# rover_5.net
KiCad netlist of a schematic drawn in EAGLE
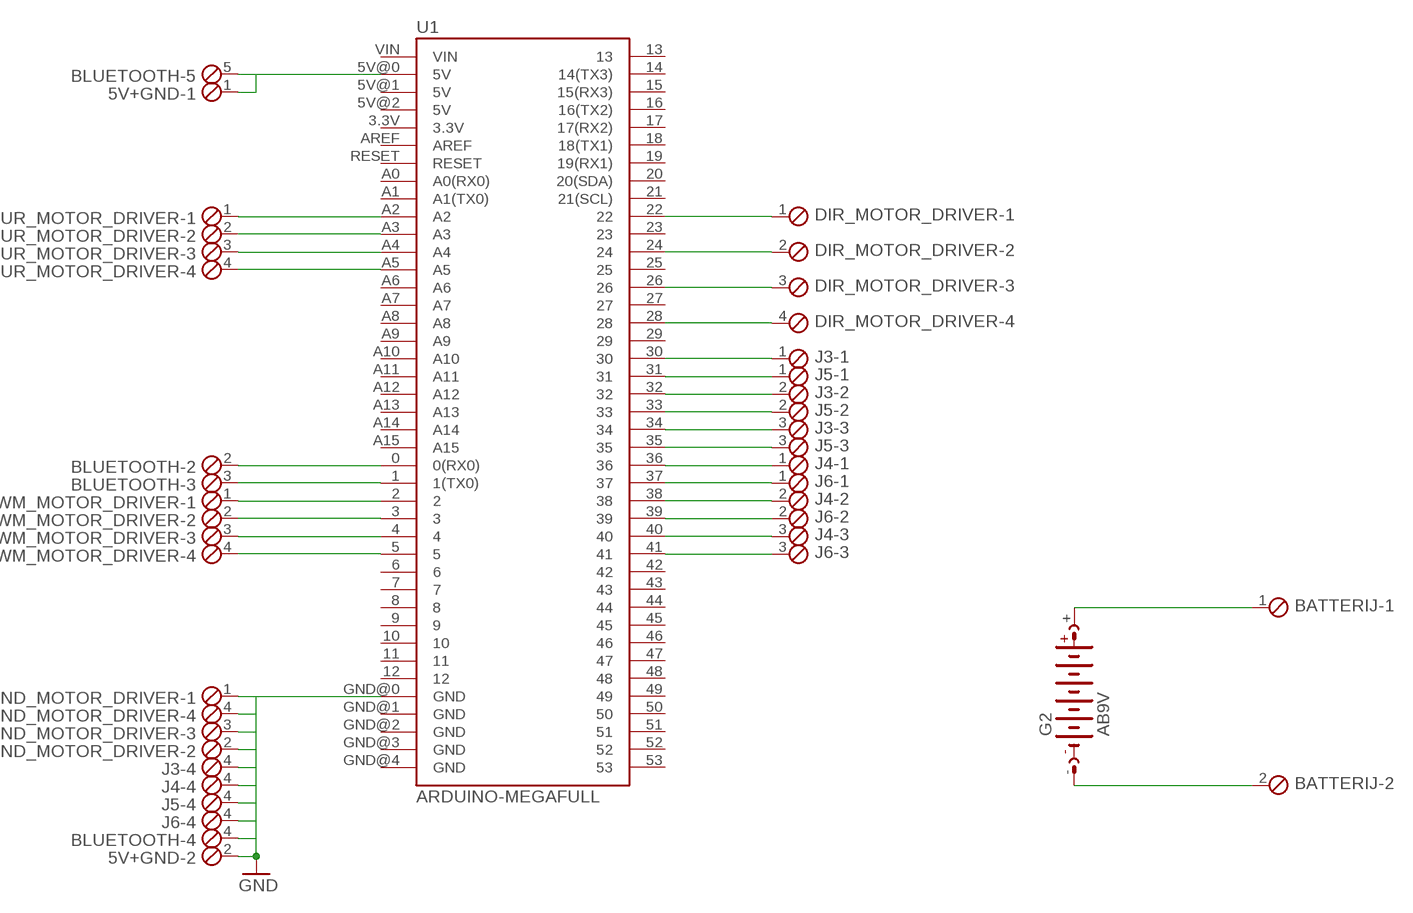
[diagram p0: schematic, sheet 1]

(export (version "E")
  (design (tool "Eeschema 10.0.6"))
  (components
    (comp (ref "5V+GND")
      (value "MPT2")
      (footprint "eagle-import:2POL254")
      (libsource (lib "eagle-import") (part "MPT2"))
    )
    (comp (ref "BATTERIJ")
      (value "MPT2")
      (footprint "eagle-import:2POL254")
      (libsource (lib "eagle-import") (part "MPT2"))
    )
    (comp (ref "BLUETOOTH")
      (value "MPT6")
      (footprint "eagle-import:6POL254")
      (libsource (lib "eagle-import") (part "MPT6"))
    )
    (comp (ref "CUR_MOTOR_DRIVER")
      (value "MPT4")
      (footprint "eagle-import:4POL254")
      (libsource (lib "eagle-import") (part "MPT4"))
    )
    (comp (ref "DIR_MOTOR_DRIVER")
      (value "MPT4")
      (footprint "eagle-import:4POL254")
      (libsource (lib "eagle-import") (part "MPT4"))
    )
    (comp (ref "G2")
      (value "AB9V")
      (footprint "eagle-import:AB9V")
      (libsource (lib "eagle-import") (part "AB9V"))
    )
    (comp (ref "GND_MOTOR_DRIVER")
      (value "MPT4")
      (footprint "eagle-import:4POL254")
      (libsource (lib "eagle-import") (part "MPT4"))
    )
    (comp (ref "J3")
      (value "MPT4")
      (footprint "eagle-import:4POL254")
      (libsource (lib "eagle-import") (part "MPT4"))
    )
    (comp (ref "J4")
      (value "MPT4")
      (footprint "eagle-import:4POL254")
      (libsource (lib "eagle-import") (part "MPT4"))
    )
    (comp (ref "J5")
      (value "MPT4")
      (footprint "eagle-import:4POL254")
      (libsource (lib "eagle-import") (part "MPT4"))
    )
    (comp (ref "J6")
      (value "MPT4")
      (footprint "eagle-import:4POL254")
      (libsource (lib "eagle-import") (part "MPT4"))
    )
    (comp (ref "PWM_MOTOR_DRIVER")
      (value "MPT4")
      (footprint "eagle-import:4POL254")
      (libsource (lib "eagle-import") (part "MPT4"))
    )
    (comp (ref "U1")
      (value "ARDUINO-MEGAFULL")
      (footprint "eagle-import:ARDUINO_MEGA")
      (libsource (lib "eagle-import") (part "ARDUINO-MEGAFULL"))
    )
  )
  (nets
    (net (code "1") (name "GND") (class "Default")
      (node (ref "5V+GND") (pin "2") (pinfunction "1_2") (pintype "passive"))
      (node (ref "BLUETOOTH") (pin "4") (pinfunction "1_4") (pintype "passive"))
      (node (ref "GND_MOTOR_DRIVER") (pin "1") (pinfunction "1_1") (pintype "passive"))
      (node (ref "GND_MOTOR_DRIVER") (pin "2") (pinfunction "1_2") (pintype "passive"))
      (node (ref "GND_MOTOR_DRIVER") (pin "3") (pinfunction "1_3") (pintype "passive"))
      (node (ref "GND_MOTOR_DRIVER") (pin "4") (pinfunction "1_4") (pintype "passive"))
      (node (ref "J3") (pin "4") (pinfunction "1_4") (pintype "passive"))
      (node (ref "J4") (pin "4") (pinfunction "1_4") (pintype "passive"))
      (node (ref "J5") (pin "4") (pinfunction "1_4") (pintype "passive"))
      (node (ref "J6") (pin "4") (pinfunction "1_4") (pintype "passive"))
      (node (ref "U1") (pin "GND@0") (pinfunction "GND_GND@0") (pintype "bidirectional"))
    )
    (net (code "2") (name "Net-(BATTERIJ-Pad1)") (class "Default")
      (node (ref "BATTERIJ") (pin "1") (pinfunction "1_1") (pintype "passive"))
      (node (ref "G2") (pin "+") (pinfunction "+_+") (pintype "passive"))
    )
    (net (code "3") (name "Net-(BATTERIJB-1)") (class "Default")
      (node (ref "BATTERIJ") (pin "2") (pinfunction "1_2") (pintype "passive"))
      (node (ref "G2") (pin "-") (pinfunction "-_-") (pintype "passive"))
    )
    (net (code "4") (name "Net-(BLUETOOTHB-1)") (class "Default")
      (node (ref "BLUETOOTH") (pin "2") (pinfunction "1_2") (pintype "passive"))
      (node (ref "U1") (pin "0") (pinfunction "0(RX0)_0") (pintype "bidirectional"))
    )
    (net (code "5") (name "Net-(BLUETOOTHC-1)") (class "Default")
      (node (ref "BLUETOOTH") (pin "3") (pinfunction "1_3") (pintype "passive"))
      (node (ref "U1") (pin "1") (pinfunction "1(TX0)_1") (pintype "bidirectional"))
    )
    (net (code "6") (name "Net-(BLUETOOTHE-1)") (class "Default")
      (node (ref "5V+GND") (pin "1") (pinfunction "1_1") (pintype "passive"))
      (node (ref "BLUETOOTH") (pin "5") (pinfunction "1_5") (pintype "passive"))
      (node (ref "U1") (pin "5V@0") (pinfunction "5V_5V@0") (pintype "bidirectional"))
    )
    (net (code "7") (name "Net-(CUR_MOTOR_DRIVER-Pad1)") (class "Default")
      (node (ref "CUR_MOTOR_DRIVER") (pin "1") (pinfunction "1_1") (pintype "passive"))
      (node (ref "U1") (pin "A2") (pinfunction "A2_A2") (pintype "bidirectional"))
    )
    (net (code "8") (name "Net-(CUR_MOTOR_DRIVERB-1)") (class "Default")
      (node (ref "CUR_MOTOR_DRIVER") (pin "2") (pinfunction "1_2") (pintype "passive"))
      (node (ref "U1") (pin "A3") (pinfunction "A3_A3") (pintype "bidirectional"))
    )
    (net (code "9") (name "Net-(CUR_MOTOR_DRIVERC-1)") (class "Default")
      (node (ref "CUR_MOTOR_DRIVER") (pin "3") (pinfunction "1_3") (pintype "passive"))
      (node (ref "U1") (pin "A4") (pinfunction "A4_A4") (pintype "bidirectional"))
    )
    (net (code "10") (name "Net-(CUR_MOTOR_DRIVERD-1)") (class "Default")
      (node (ref "CUR_MOTOR_DRIVER") (pin "4") (pinfunction "1_4") (pintype "passive"))
      (node (ref "U1") (pin "A5") (pinfunction "A5_A5") (pintype "bidirectional"))
    )
    (net (code "11") (name "Net-(DIR_MOTOR_DRIVER-Pad1)") (class "Default")
      (node (ref "DIR_MOTOR_DRIVER") (pin "1") (pinfunction "1_1") (pintype "passive"))
      (node (ref "U1") (pin "22") (pinfunction "22_22") (pintype "bidirectional"))
    )
    (net (code "12") (name "Net-(DIR_MOTOR_DRIVERB-1)") (class "Default")
      (node (ref "DIR_MOTOR_DRIVER") (pin "2") (pinfunction "1_2") (pintype "passive"))
      (node (ref "U1") (pin "24") (pinfunction "24_24") (pintype "bidirectional"))
    )
    (net (code "13") (name "Net-(DIR_MOTOR_DRIVERC-1)") (class "Default")
      (node (ref "DIR_MOTOR_DRIVER") (pin "3") (pinfunction "1_3") (pintype "passive"))
      (node (ref "U1") (pin "26") (pinfunction "26_26") (pintype "bidirectional"))
    )
    (net (code "14") (name "Net-(DIR_MOTOR_DRIVERD-1)") (class "Default")
      (node (ref "DIR_MOTOR_DRIVER") (pin "4") (pinfunction "1_4") (pintype "passive"))
      (node (ref "U1") (pin "28") (pinfunction "28_28") (pintype "bidirectional"))
    )
    (net (code "15") (name "Net-(J3-Pad1)") (class "Default")
      (node (ref "J3") (pin "1") (pinfunction "1_1") (pintype "passive"))
      (node (ref "U1") (pin "30") (pinfunction "30_30") (pintype "bidirectional"))
    )
    (net (code "16") (name "Net-(J3B-1)") (class "Default")
      (node (ref "J3") (pin "2") (pinfunction "1_2") (pintype "passive"))
      (node (ref "U1") (pin "32") (pinfunction "32_32") (pintype "bidirectional"))
    )
    (net (code "17") (name "Net-(J3C-1)") (class "Default")
      (node (ref "J3") (pin "3") (pinfunction "1_3") (pintype "passive"))
      (node (ref "U1") (pin "34") (pinfunction "34_34") (pintype "bidirectional"))
    )
    (net (code "18") (name "Net-(J4-Pad1)") (class "Default")
      (node (ref "J4") (pin "1") (pinfunction "1_1") (pintype "passive"))
      (node (ref "U1") (pin "36") (pinfunction "36_36") (pintype "bidirectional"))
    )
    (net (code "19") (name "Net-(J4B-1)") (class "Default")
      (node (ref "J4") (pin "2") (pinfunction "1_2") (pintype "passive"))
      (node (ref "U1") (pin "38") (pinfunction "38_38") (pintype "bidirectional"))
    )
    (net (code "20") (name "Net-(J4C-1)") (class "Default")
      (node (ref "J4") (pin "3") (pinfunction "1_3") (pintype "passive"))
      (node (ref "U1") (pin "40") (pinfunction "40_40") (pintype "bidirectional"))
    )
    (net (code "21") (name "Net-(J5-Pad1)") (class "Default")
      (node (ref "J5") (pin "1") (pinfunction "1_1") (pintype "passive"))
      (node (ref "U1") (pin "31") (pinfunction "31_31") (pintype "bidirectional"))
    )
    (net (code "22") (name "Net-(J5B-1)") (class "Default")
      (node (ref "J5") (pin "2") (pinfunction "1_2") (pintype "passive"))
      (node (ref "U1") (pin "33") (pinfunction "33_33") (pintype "bidirectional"))
    )
    (net (code "23") (name "Net-(J5C-1)") (class "Default")
      (node (ref "J5") (pin "3") (pinfunction "1_3") (pintype "passive"))
      (node (ref "U1") (pin "35") (pinfunction "35_35") (pintype "bidirectional"))
    )
    (net (code "24") (name "Net-(J6-Pad1)") (class "Default")
      (node (ref "J6") (pin "1") (pinfunction "1_1") (pintype "passive"))
      (node (ref "U1") (pin "37") (pinfunction "37_37") (pintype "bidirectional"))
    )
    (net (code "25") (name "Net-(J6B-1)") (class "Default")
      (node (ref "J6") (pin "2") (pinfunction "1_2") (pintype "passive"))
      (node (ref "U1") (pin "39") (pinfunction "39_39") (pintype "bidirectional"))
    )
    (net (code "26") (name "Net-(J6C-1)") (class "Default")
      (node (ref "J6") (pin "3") (pinfunction "1_3") (pintype "passive"))
      (node (ref "U1") (pin "41") (pinfunction "41_41") (pintype "bidirectional"))
    )
    (net (code "27") (name "Net-(PWM_MOTOR_DRIVER-Pad1)") (class "Default")
      (node (ref "PWM_MOTOR_DRIVER") (pin "1") (pinfunction "1_1") (pintype "passive"))
      (node (ref "U1") (pin "2") (pinfunction "2_2") (pintype "bidirectional"))
    )
    (net (code "28") (name "Net-(PWM_MOTOR_DRIVERB-1)") (class "Default")
      (node (ref "PWM_MOTOR_DRIVER") (pin "2") (pinfunction "1_2") (pintype "passive"))
      (node (ref "U1") (pin "3") (pinfunction "3_3") (pintype "bidirectional"))
    )
    (net (code "29") (name "Net-(PWM_MOTOR_DRIVERC-1)") (class "Default")
      (node (ref "PWM_MOTOR_DRIVER") (pin "3") (pinfunction "1_3") (pintype "passive"))
      (node (ref "U1") (pin "4") (pinfunction "4_4") (pintype "bidirectional"))
    )
    (net (code "30") (name "Net-(PWM_MOTOR_DRIVERD-1)") (class "Default")
      (node (ref "PWM_MOTOR_DRIVER") (pin "4") (pinfunction "1_4") (pintype "passive"))
      (node (ref "U1") (pin "5") (pinfunction "5_5") (pintype "bidirectional"))
    )
    (net (code "31") (name "unconnected-(U1-5V-Pad5V@1)") (class "Default")
      (node (ref "U1") (pin "5V@1") (pinfunction "5V_5V@1") (pintype "bidirectional"))
    )
    (net (code "32") (name "unconnected-(U1-5V-Pad5V@2)") (class "Default")
      (node (ref "U1") (pin "5V@2") (pinfunction "5V_5V@2") (pintype "bidirectional"))
    )
    (net (code "33") (name "unconnected-(U1-14(TX3)-Pad14)") (class "Default")
      (node (ref "U1") (pin "14") (pinfunction "14(TX3)_14") (pintype "bidirectional"))
    )
    (net (code "34") (name "unconnected-(U1-15(RX3)-Pad15)") (class "Default")
      (node (ref "U1") (pin "15") (pinfunction "15(RX3)_15") (pintype "bidirectional"))
    )
    (net (code "35") (name "unconnected-(U1-16(TX2)-Pad16)") (class "Default")
      (node (ref "U1") (pin "16") (pinfunction "16(TX2)_16") (pintype "bidirectional"))
    )
    (net (code "36") (name "unconnected-(U1-17(RX2)-Pad17)") (class "Default")
      (node (ref "U1") (pin "17") (pinfunction "17(RX2)_17") (pintype "bidirectional"))
    )
    (net (code "37") (name "unconnected-(U1-18(TX1)-Pad18)") (class "Default")
      (node (ref "U1") (pin "18") (pinfunction "18(TX1)_18") (pintype "bidirectional"))
    )
    (net (code "38") (name "unconnected-(U1-19(RX1)-Pad19)") (class "Default")
      (node (ref "U1") (pin "19") (pinfunction "19(RX1)_19") (pintype "bidirectional"))
    )
    (net (code "39") (name "unconnected-(U1-20(SDA)-Pad20)") (class "Default")
      (node (ref "U1") (pin "20") (pinfunction "20(SDA)_20") (pintype "bidirectional"))
    )
    (net (code "40") (name "unconnected-(U1-21(SCL)-Pad21)") (class "Default")
      (node (ref "U1") (pin "21") (pinfunction "21(SCL)_21") (pintype "bidirectional"))
    )
    (net (code "41") (name "unconnected-(U1-A0(RX0)-PadA0)") (class "Default")
      (node (ref "U1") (pin "A0") (pinfunction "A0(RX0)_A0") (pintype "bidirectional"))
    )
    (net (code "42") (name "unconnected-(U1-A1(TX0)-PadA1)") (class "Default")
      (node (ref "U1") (pin "A1") (pinfunction "A1(TX0)_A1") (pintype "bidirectional"))
    )
    (net (code "43") (name "unconnected-(U1-GND-PadGND@1)") (class "Default")
      (node (ref "U1") (pin "GND@1") (pinfunction "GND_GND@1") (pintype "bidirectional"))
    )
    (net (code "44") (name "unconnected-(U1-GND-PadGND@2)") (class "Default")
      (node (ref "U1") (pin "GND@2") (pinfunction "GND_GND@2") (pintype "bidirectional"))
    )
    (net (code "45") (name "unconnected-(U1-GND-PadGND@3)") (class "Default")
      (node (ref "U1") (pin "GND@3") (pinfunction "GND_GND@3") (pintype "bidirectional"))
    )
    (net (code "46") (name "unconnected-(U1-GND-PadGND@4)") (class "Default")
      (node (ref "U1") (pin "GND@4") (pinfunction "GND_GND@4") (pintype "bidirectional"))
    )
    (net (code "47") (name "unconnected-(U1-Pad3.3V)") (class "Default")
      (node (ref "U1") (pin "3.3V") (pinfunction "3.3V_3.3V") (pintype "bidirectional"))
    )
    (net (code "48") (name "unconnected-(U1-Pad6)") (class "Default")
      (node (ref "U1") (pin "6") (pinfunction "6_6") (pintype "bidirectional"))
    )
    (net (code "49") (name "unconnected-(U1-Pad7)") (class "Default")
      (node (ref "U1") (pin "7") (pinfunction "7_7") (pintype "bidirectional"))
    )
    (net (code "50") (name "unconnected-(U1-Pad8)") (class "Default")
      (node (ref "U1") (pin "8") (pinfunction "8_8") (pintype "bidirectional"))
    )
    (net (code "51") (name "unconnected-(U1-Pad9)") (class "Default")
      (node (ref "U1") (pin "9") (pinfunction "9_9") (pintype "bidirectional"))
    )
    (net (code "52") (name "unconnected-(U1-Pad10)") (class "Default")
      (node (ref "U1") (pin "10") (pinfunction "10_10") (pintype "bidirectional"))
    )
    (net (code "53") (name "unconnected-(U1-Pad11)") (class "Default")
      (node (ref "U1") (pin "11") (pinfunction "11_11") (pintype "bidirectional"))
    )
    (net (code "54") (name "unconnected-(U1-Pad12)") (class "Default")
      (node (ref "U1") (pin "12") (pinfunction "12_12") (pintype "bidirectional"))
    )
    (net (code "55") (name "unconnected-(U1-Pad13)") (class "Default")
      (node (ref "U1") (pin "13") (pinfunction "13_13") (pintype "bidirectional"))
    )
    (net (code "56") (name "unconnected-(U1-Pad23)") (class "Default")
      (node (ref "U1") (pin "23") (pinfunction "23_23") (pintype "bidirectional"))
    )
    (net (code "57") (name "unconnected-(U1-Pad25)") (class "Default")
      (node (ref "U1") (pin "25") (pinfunction "25_25") (pintype "bidirectional"))
    )
    (net (code "58") (name "unconnected-(U1-Pad27)") (class "Default")
      (node (ref "U1") (pin "27") (pinfunction "27_27") (pintype "bidirectional"))
    )
    (net (code "59") (name "unconnected-(U1-Pad29)") (class "Default")
      (node (ref "U1") (pin "29") (pinfunction "29_29") (pintype "bidirectional"))
    )
    (net (code "60") (name "unconnected-(U1-Pad42)") (class "Default")
      (node (ref "U1") (pin "42") (pinfunction "42_42") (pintype "bidirectional"))
    )
    (net (code "61") (name "unconnected-(U1-Pad43)") (class "Default")
      (node (ref "U1") (pin "43") (pinfunction "43_43") (pintype "bidirectional"))
    )
    (net (code "62") (name "unconnected-(U1-Pad44)") (class "Default")
      (node (ref "U1") (pin "44") (pinfunction "44_44") (pintype "bidirectional"))
    )
    (net (code "63") (name "unconnected-(U1-Pad45)") (class "Default")
      (node (ref "U1") (pin "45") (pinfunction "45_45") (pintype "bidirectional"))
    )
    (net (code "64") (name "unconnected-(U1-Pad46)") (class "Default")
      (node (ref "U1") (pin "46") (pinfunction "46_46") (pintype "bidirectional"))
    )
    (net (code "65") (name "unconnected-(U1-Pad47)") (class "Default")
      (node (ref "U1") (pin "47") (pinfunction "47_47") (pintype "bidirectional"))
    )
    (net (code "66") (name "unconnected-(U1-Pad48)") (class "Default")
      (node (ref "U1") (pin "48") (pinfunction "48_48") (pintype "bidirectional"))
    )
    (net (code "67") (name "unconnected-(U1-Pad49)") (class "Default")
      (node (ref "U1") (pin "49") (pinfunction "49_49") (pintype "bidirectional"))
    )
    (net (code "68") (name "unconnected-(U1-Pad50)") (class "Default")
      (node (ref "U1") (pin "50") (pinfunction "50_50") (pintype "bidirectional"))
    )
    (net (code "69") (name "unconnected-(U1-Pad51)") (class "Default")
      (node (ref "U1") (pin "51") (pinfunction "51_51") (pintype "bidirectional"))
    )
    (net (code "70") (name "unconnected-(U1-Pad52)") (class "Default")
      (node (ref "U1") (pin "52") (pinfunction "52_52") (pintype "bidirectional"))
    )
    (net (code "71") (name "unconnected-(U1-Pad53)") (class "Default")
      (node (ref "U1") (pin "53") (pinfunction "53_53") (pintype "bidirectional"))
    )
    (net (code "72") (name "unconnected-(U1-PadA6)") (class "Default")
      (node (ref "U1") (pin "A6") (pinfunction "A6_A6") (pintype "bidirectional"))
    )
    (net (code "73") (name "unconnected-(U1-PadA7)") (class "Default")
      (node (ref "U1") (pin "A7") (pinfunction "A7_A7") (pintype "bidirectional"))
    )
    (net (code "74") (name "unconnected-(U1-PadA8)") (class "Default")
      (node (ref "U1") (pin "A8") (pinfunction "A8_A8") (pintype "bidirectional"))
    )
    (net (code "75") (name "unconnected-(U1-PadA9)") (class "Default")
      (node (ref "U1") (pin "A9") (pinfunction "A9_A9") (pintype "bidirectional"))
    )
    (net (code "76") (name "unconnected-(U1-PadA10)") (class "Default")
      (node (ref "U1") (pin "A10") (pinfunction "A10_A10") (pintype "bidirectional"))
    )
    (net (code "77") (name "unconnected-(U1-PadA11)") (class "Default")
      (node (ref "U1") (pin "A11") (pinfunction "A11_A11") (pintype "bidirectional"))
    )
    (net (code "78") (name "unconnected-(U1-PadA12)") (class "Default")
      (node (ref "U1") (pin "A12") (pinfunction "A12_A12") (pintype "bidirectional"))
    )
    (net (code "79") (name "unconnected-(U1-PadA13)") (class "Default")
      (node (ref "U1") (pin "A13") (pinfunction "A13_A13") (pintype "bidirectional"))
    )
    (net (code "80") (name "unconnected-(U1-PadA14)") (class "Default")
      (node (ref "U1") (pin "A14") (pinfunction "A14_A14") (pintype "bidirectional"))
    )
    (net (code "81") (name "unconnected-(U1-PadA15)") (class "Default")
      (node (ref "U1") (pin "A15") (pinfunction "A15_A15") (pintype "bidirectional"))
    )
    (net (code "82") (name "unconnected-(U1-PadAREF)") (class "Default")
      (node (ref "U1") (pin "AREF") (pinfunction "AREF_AREF") (pintype "bidirectional"))
    )
    (net (code "83") (name "unconnected-(U1-PadRESET)") (class "Default")
      (node (ref "U1") (pin "RESET") (pinfunction "RESET_RESET") (pintype "bidirectional"))
    )
    (net (code "84") (name "unconnected-(U1-PadVIN)") (class "Default")
      (node (ref "U1") (pin "VIN") (pinfunction "VIN_VIN") (pintype "bidirectional"))
    )
  )
)
